# 2-Supplies.net
KiCad netlist of a schematic drawn in Altium Designer
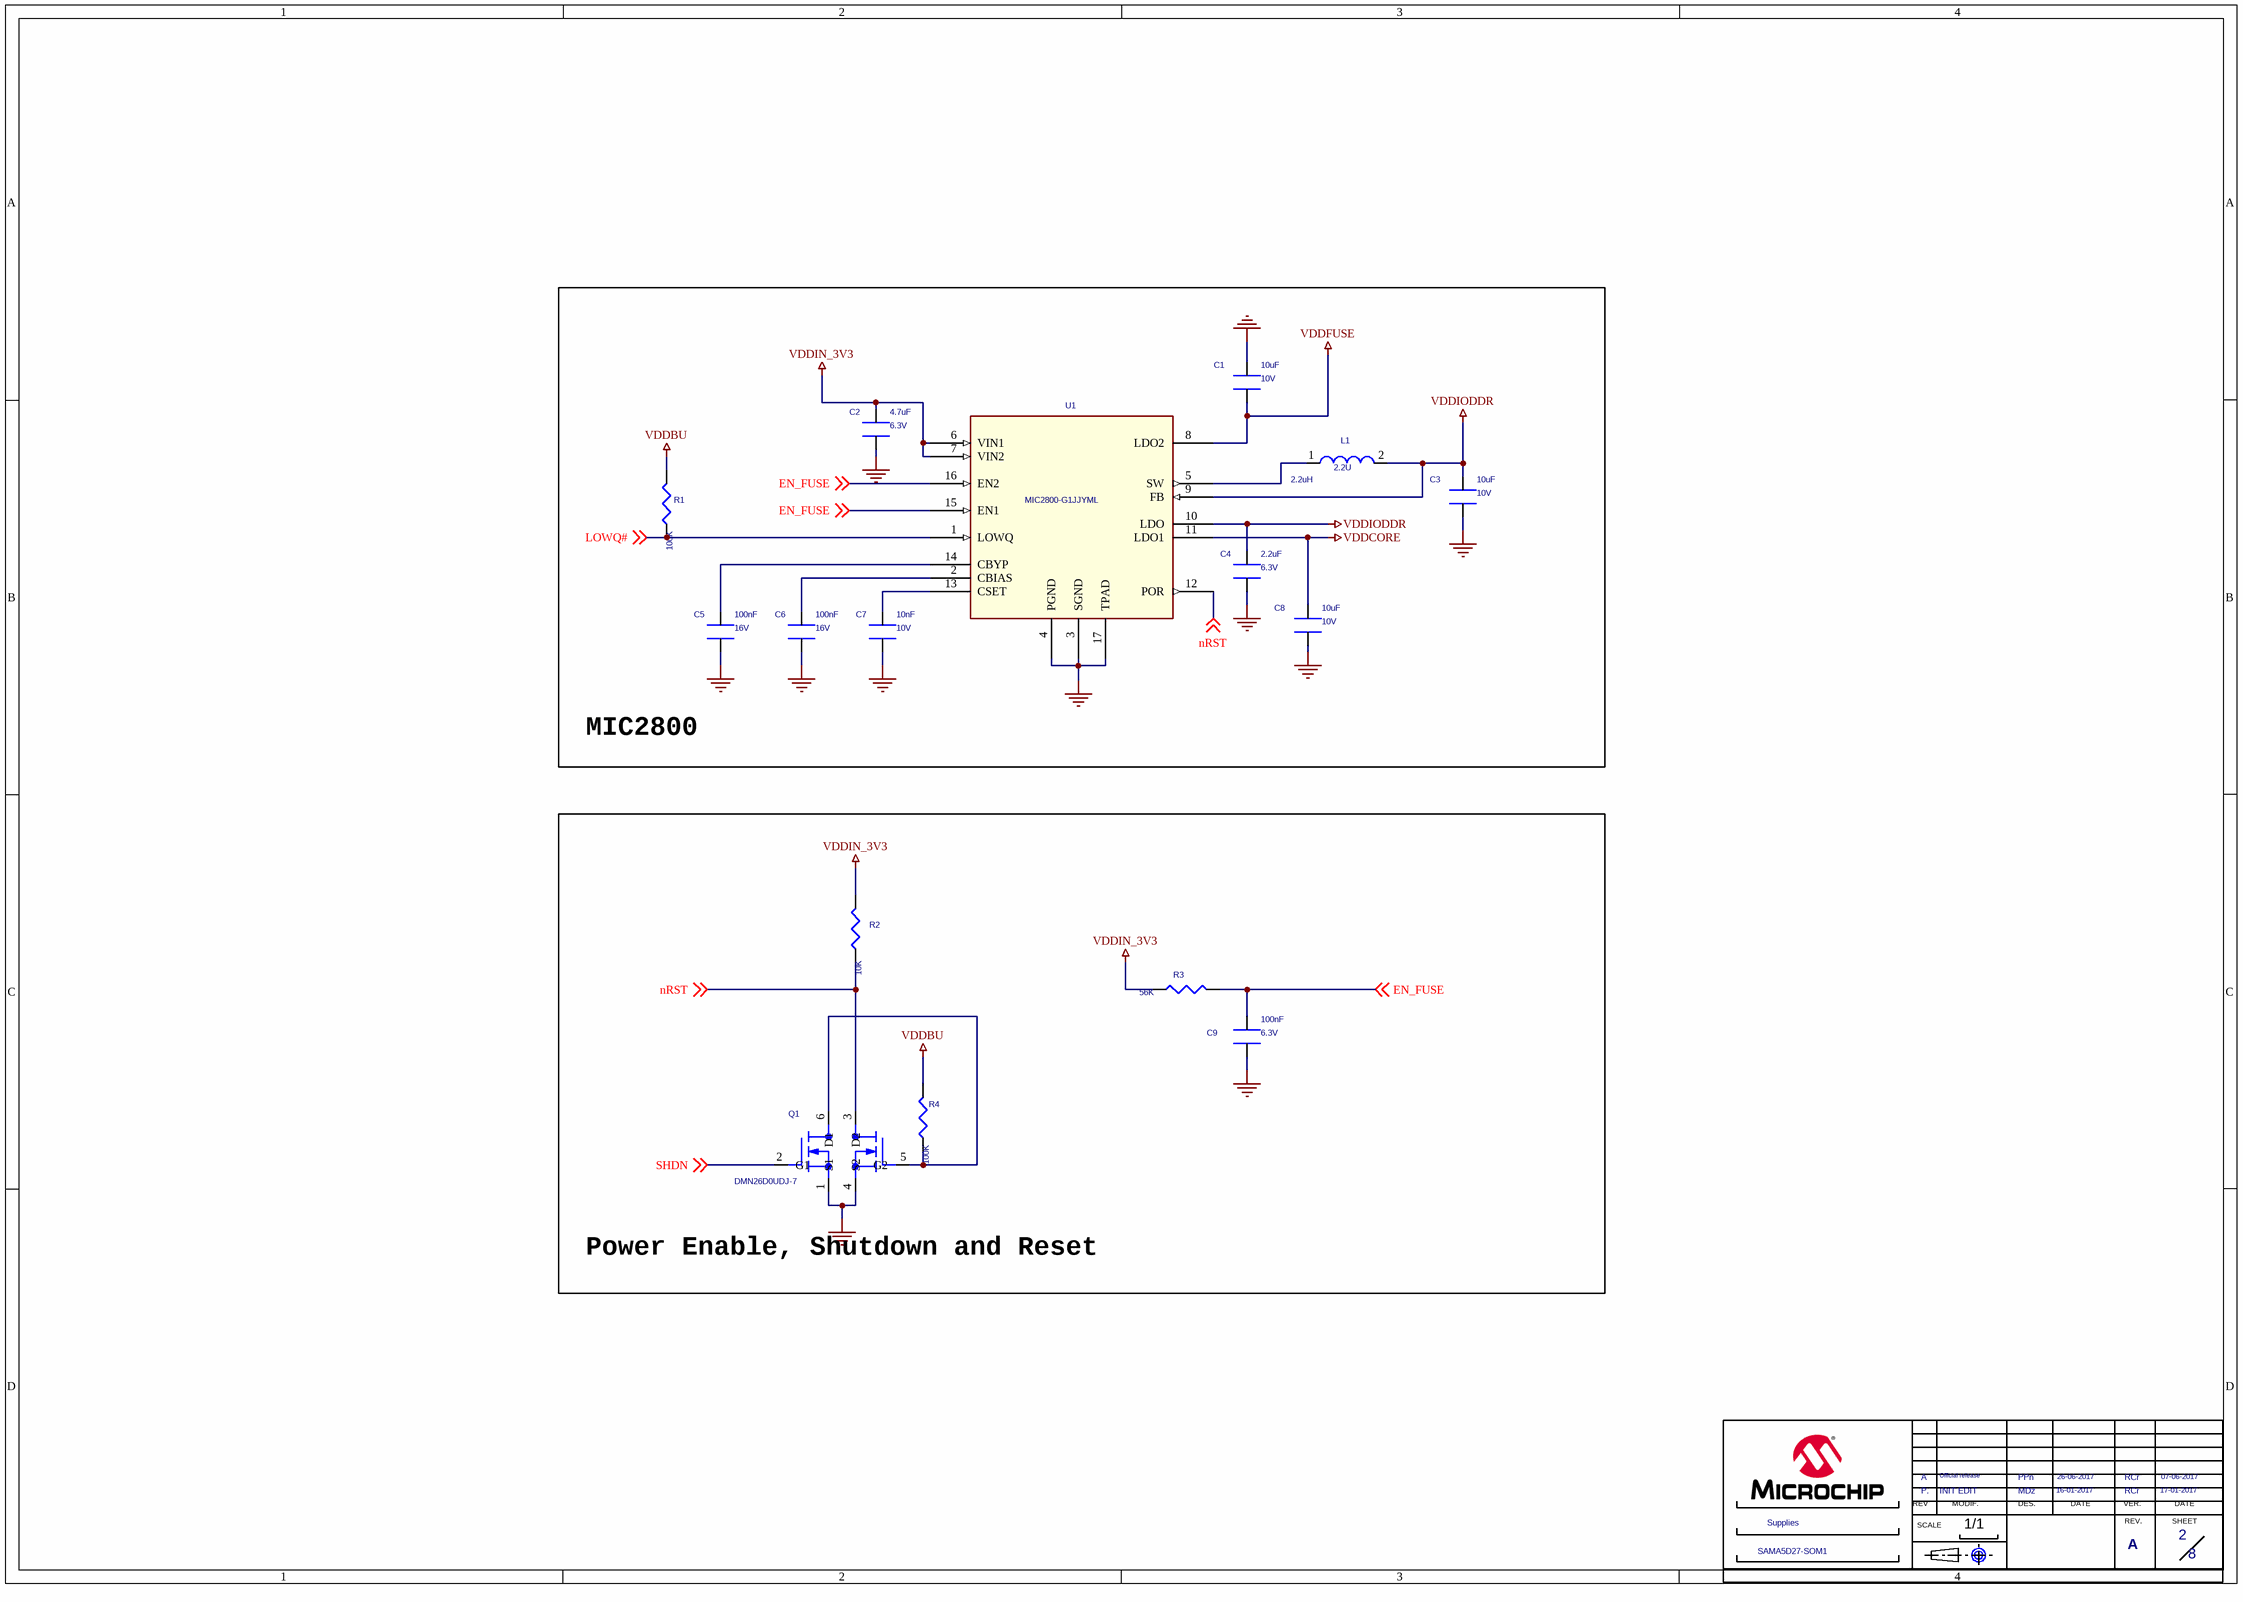
[diagram p0: 2-Supplies.SchDoc]

(export (version "E")
  (design (tool "Eeschema 10.0.6"))
  (components
    (comp (ref "C1")
      (value "xpF x% xV")
      (footprint "C0603")
      (fields (field (name "TENSION") "10V") (field (name "VALEUR") "10uF") (field (name "HAUTEUR") "xmm"))
      (libsource (lib "*") (part "C0603-10uF-X5R-10V-10%"))
    )
    (comp (ref "C2")
      (value "xpF x% xV")
      (footprint "C0402")
      (fields (field (name "TENSION") "6.3V") (field (name "VALEUR") "4.7uF") (field (name "HAUTEUR") "xmm"))
      (libsource (lib "*") (part "C0402-4.7uF-X5R-6.3V-10%"))
    )
    (comp (ref "C3")
      (value "xpF x% xV")
      (footprint "C0603")
      (fields (field (name "TENSION") "10V") (field (name "VALEUR") "10uF") (field (name "HAUTEUR") "xmm"))
      (libsource (lib "*") (part "C0603-10uF-X5R-10V-10%"))
    )
    (comp (ref "C4")
      (value "xpF x% xV")
      (footprint "C0603")
      (fields (field (name "TENSION") "6.3V") (field (name "VALEUR") "2.2uF") (field (name "HAUTEUR") "xmm"))
      (libsource (lib "*") (part "C0603-2.2uF-X7R-6.3V-10%"))
    )
    (comp (ref "C5")
      (value "xpF x% xV")
      (footprint "C0402")
      (fields (field (name "TENSION") "16V") (field (name "VALEUR") "100nF") (field (name "HAUTEUR") "xmm"))
      (libsource (lib "*") (part "C0402-100nF-X7R-16V-10%"))
    )
    (comp (ref "C6")
      (value "xpF x% xV")
      (footprint "C0402")
      (fields (field (name "TENSION") "16V") (field (name "VALEUR") "100nF") (field (name "HAUTEUR") "xmm"))
      (libsource (lib "*") (part "C0402-100nF-X7R-16V-10%"))
    )
    (comp (ref "C7")
      (value "xpF x% xV")
      (footprint "C0201")
      (fields (field (name "TENSION") "10V") (field (name "VALEUR") "10nF") (field (name "HAUTEUR") "xmm"))
      (libsource (lib "*") (part "C0201-10nF-X7R-10V"))
    )
    (comp (ref "C8")
      (value "xpF x% xV")
      (footprint "C0603")
      (fields (field (name "TENSION") "10V") (field (name "VALEUR") "10uF") (field (name "HAUTEUR") "xmm"))
      (libsource (lib "*") (part "C0603-10uF-X5R-10V-10%"))
    )
    (comp (ref "C9")
      (value "xpF x% xV")
      (footprint "C0201")
      (fields (field (name "VALEUR") "100nF") (field (name "TENSION") "6.3V") (field (name "HAUTEUR") "xmm"))
      (libsource (lib "*") (part "C0201-100nF-X5R-6.3V"))
    )
    (comp (ref "L1")
      (value "2.2U")
      (footprint "L2520")
      (fields
        (field (name "TOLERANCE") "20%")
        (field (name "PARTNUMBER") "MLP2520H2R2MT0S1")
        (field (name "VALEUR") "2.2uH")
      )
      (libsource (lib "*") (part "MLP2520H2R2MT0S1"))
    )
    (comp (ref "Q1")
      (value "DMN26D0UDJ-7")
      (footprint "SOT963_01")
      (libsource (lib "*") (part "DMN26D0UDJ-7"))
    )
    (comp (ref "R1")
      (value "xR x% xW")
      (footprint "R0201")
      (fields (field (name "VALEUR") "100K") (field (name "TOLERANCE") "5%"))
      (libsource (lib "*") (part "R0201-100K-5%"))
    )
    (comp (ref "R2")
      (value "xR x% xW")
      (footprint "R0201")
      (fields (field (name "VALEUR") "10K") (field (name "TOLERANCE") "5%"))
      (libsource (lib "*") (part "R0201-10K-5%"))
    )
    (comp (ref "R3")
      (value "xR x% xW")
      (footprint "R0201")
      (fields (field (name "TOLERANCE") "5%") (field (name "VALEUR") "56K"))
      (libsource (lib "*") (part "R0201-56K-5%"))
    )
    (comp (ref "R4")
      (value "xR x% xW")
      (footprint "R0201")
      (fields (field (name "VALEUR") "100K") (field (name "TOLERANCE") "5%"))
      (libsource (lib "*") (part "R0201-100K-5%"))
    )
    (comp (ref "U1")
      (value "MIC2800-G1JJYML")
      (footprint "QFN16_02")
      (libsource (lib "*") (part "MIC2800-G1JJYML"))
    )
  )
  (nets
    (net (code "1") (name "EN_FUSE") (class "Default")
      (node (ref "C9") (pin "2") (pinfunction "2_2") (pintype "passive"))
      (node (ref "R3") (pin "2") (pinfunction "2_2") (pintype "passive"))
      (node (ref "U1") (pin "15") (pinfunction "EN1_15") (pintype "input"))
      (node (ref "U1") (pin "16") (pinfunction "EN2_16") (pintype "input"))
    )
    (net (code "2") (name "GND") (class "Default")
      (node (ref "C1") (pin "2") (pinfunction "2_2") (pintype "passive"))
      (node (ref "C2") (pin "1") (pinfunction "1_1") (pintype "passive"))
      (node (ref "C3") (pin "1") (pinfunction "1_1") (pintype "passive"))
      (node (ref "C4") (pin "1") (pinfunction "1_1") (pintype "passive"))
      (node (ref "C5") (pin "1") (pinfunction "1_1") (pintype "passive"))
      (node (ref "C6") (pin "1") (pinfunction "1_1") (pintype "passive"))
      (node (ref "C7") (pin "1") (pinfunction "1_1") (pintype "passive"))
      (node (ref "C8") (pin "1") (pinfunction "1_1") (pintype "passive"))
      (node (ref "C9") (pin "1") (pinfunction "1_1") (pintype "passive"))
      (node (ref "Q1") (pin "1") (pinfunction "S1_1") (pintype "passive"))
      (node (ref "Q1") (pin "4") (pinfunction "S2_4") (pintype "passive"))
      (node (ref "U1") (pin "17") (pinfunction "TPAD_17") (pintype "power_in"))
      (node (ref "U1") (pin "3") (pinfunction "SGND_3") (pintype "power_in"))
      (node (ref "U1") (pin "4") (pinfunction "PGND_4") (pintype "power_in"))
    )
    (net (code "3") (name "LOWQ#") (class "Default")
      (node (ref "R1") (pin "1") (pinfunction "1_1") (pintype "passive"))
      (node (ref "U1") (pin "1") (pinfunction "LOWQ_1") (pintype "input"))
    )
    (net (code "4") (name "Net-(Q1-D1)") (class "Default")
      (node (ref "Q1") (pin "5") (pinfunction "G2_5") (pintype "passive"))
      (node (ref "Q1") (pin "6") (pinfunction "D1_6") (pintype "passive"))
      (node (ref "R4") (pin "1") (pinfunction "1_1") (pintype "passive"))
    )
    (net (code "5") (name "Net-(U1-CBIAS)") (class "Default")
      (node (ref "C6") (pin "2") (pinfunction "2_2") (pintype "passive"))
      (node (ref "U1") (pin "2") (pinfunction "CBIAS_2") (pintype "passive"))
    )
    (net (code "6") (name "Net-(U1-CBYP)") (class "Default")
      (node (ref "C5") (pin "2") (pinfunction "2_2") (pintype "passive"))
      (node (ref "U1") (pin "14") (pinfunction "CBYP_14") (pintype "passive"))
    )
    (net (code "7") (name "Net-(U1-CSET)") (class "Default")
      (node (ref "C7") (pin "2") (pinfunction "2_2") (pintype "passive"))
      (node (ref "U1") (pin "13") (pinfunction "CSET_13") (pintype "passive"))
    )
    (net (code "8") (name "Net-(U1-SW)") (class "Default")
      (node (ref "L1") (pin "1") (pinfunction "1_1") (pintype "passive"))
      (node (ref "U1") (pin "5") (pinfunction "SW_5") (pintype "output"))
    )
    (net (code "9") (name "SHDN") (class "Default")
      (node (ref "Q1") (pin "2") (pinfunction "G1_2") (pintype "passive"))
    )
    (net (code "10") (name "VDDBU") (class "Default")
      (node (ref "R1") (pin "2") (pinfunction "2_2") (pintype "passive"))
      (node (ref "R4") (pin "2") (pinfunction "2_2") (pintype "passive"))
    )
    (net (code "11") (name "VDDCORE") (class "Default")
      (node (ref "C8") (pin "2") (pinfunction "2_2") (pintype "passive"))
      (node (ref "U1") (pin "11") (pinfunction "LDO1_11") (pintype "power_in"))
    )
    (net (code "12") (name "VDDFUSE") (class "Default")
      (node (ref "C1") (pin "1") (pinfunction "1_1") (pintype "passive"))
      (node (ref "U1") (pin "8") (pinfunction "LDO2_8") (pintype "power_in"))
    )
    (net (code "13") (name "VDDIN_3V3") (class "Default")
      (node (ref "C2") (pin "2") (pinfunction "2_2") (pintype "passive"))
      (node (ref "R2") (pin "2") (pinfunction "2_2") (pintype "passive"))
      (node (ref "R3") (pin "1") (pinfunction "1_1") (pintype "passive"))
      (node (ref "U1") (pin "6") (pinfunction "VIN1_6") (pintype "input"))
      (node (ref "U1") (pin "7") (pinfunction "VIN2_7") (pintype "input"))
    )
    (net (code "14") (name "VDDIODDR") (class "Default")
      (node (ref "C3") (pin "2") (pinfunction "2_2") (pintype "passive"))
      (node (ref "C4") (pin "2") (pinfunction "2_2") (pintype "passive"))
      (node (ref "L1") (pin "2") (pinfunction "2_2") (pintype "passive"))
      (node (ref "U1") (pin "10") (pinfunction "LDO_10") (pintype "power_in"))
      (node (ref "U1") (pin "9") (pinfunction "FB_9") (pintype "input"))
    )
    (net (code "15") (name "nRST") (class "Default")
      (node (ref "Q1") (pin "3") (pinfunction "D2_3") (pintype "passive"))
      (node (ref "R2") (pin "1") (pinfunction "1_1") (pintype "passive"))
      (node (ref "U1") (pin "12") (pinfunction "POR_12") (pintype "output"))
    )
  )
)
